# muhtas3.net
KiCad netlist of a schematic drawn in Altium Designer
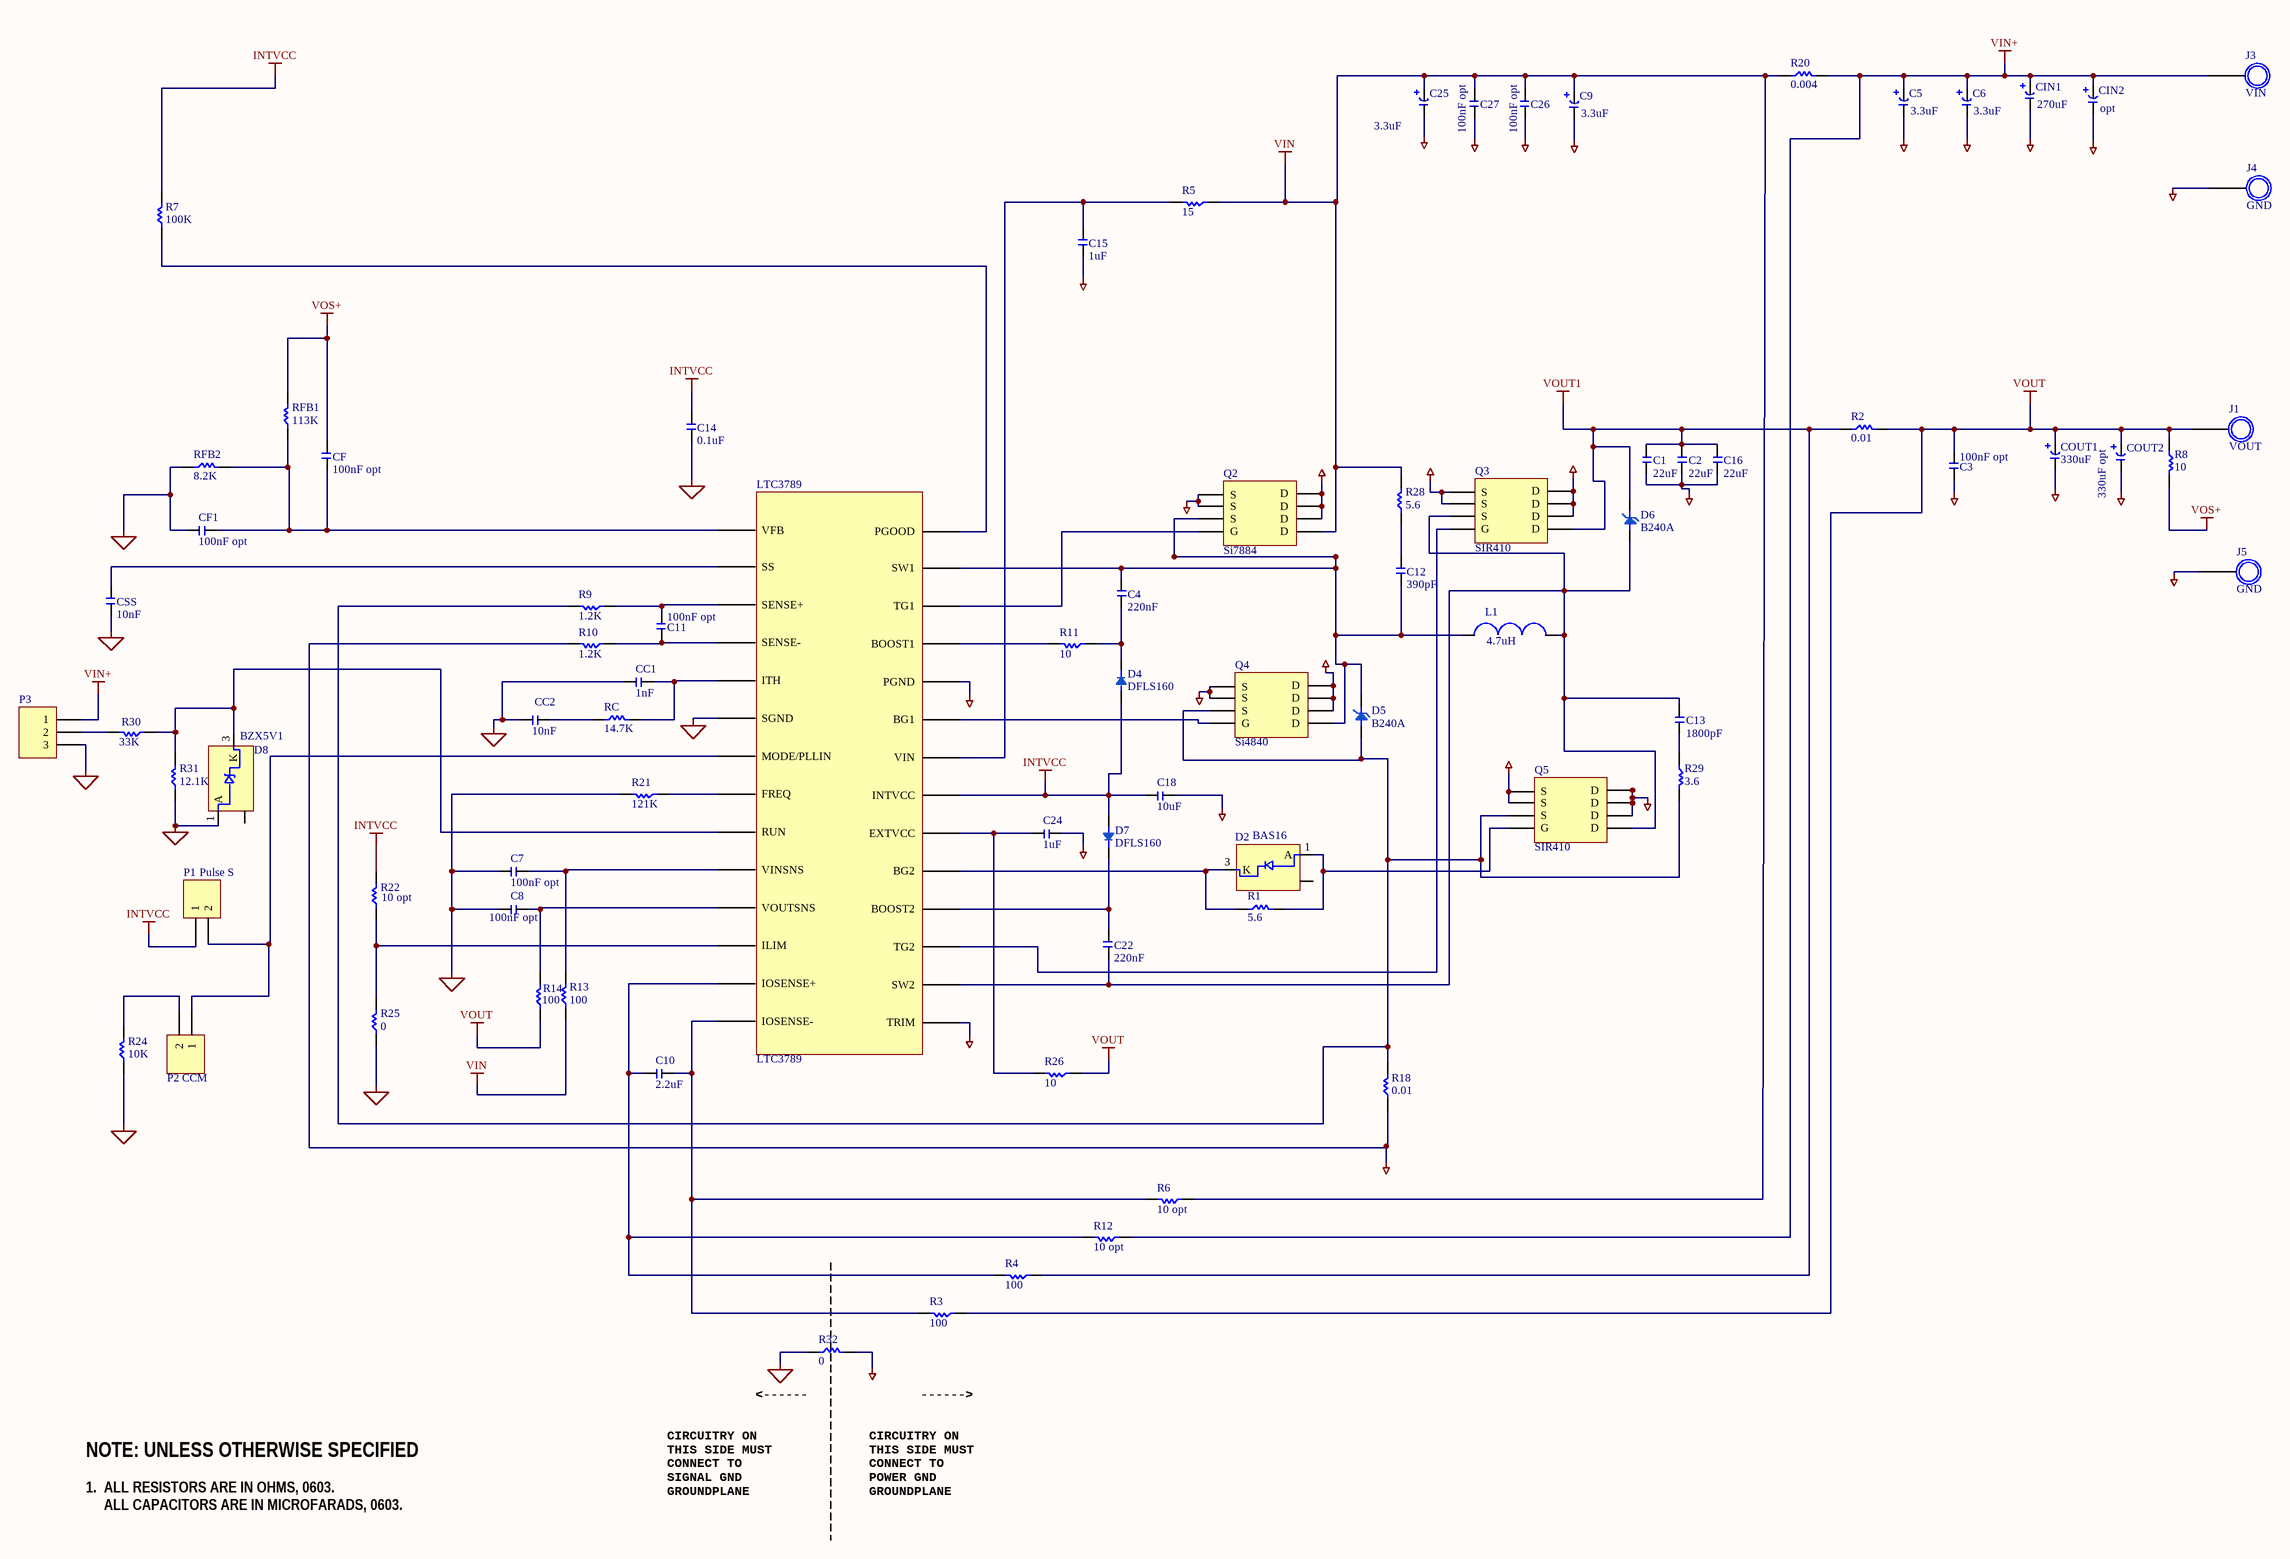
[diagram p0: muhtas3.SchDoc]

(export (version "E")
  (design (tool "Eeschema 10.0.6"))
  (components
    (comp (ref "C1")
      (value "22uF")
      (footprint "CAPC3216X190N(1206)")
      (fields
        (field (name "MANUFACTURER PART NUMBER") "VJ1206G475KXQTW1BC")
        (field (name "MANUFACTURER") "Vishay Vitramon")
        (field (name "TOLERANCE") "10%")
      )
      (libsource (lib "Database_Libs1") (part "Capacitor-non polarized"))
    )
    (comp (ref "C2")
      (value "22uF")
      (footprint "CAPC3216X190N(1206)")
      (fields
        (field (name "MANUFACTURER PART NUMBER") "VJ1206G475KXQTW1BC")
        (field (name "MANUFACTURER") "Vishay Vitramon")
        (field (name "TOLERANCE") "10%")
      )
      (libsource (lib "Database_Libs1") (part "Capacitor-non polarized"))
    )
    (comp (ref "C3")
      (value "100nF opt")
      (footprint "CAPC3216X190N(1206)")
      (fields
        (field (name "MANUFACTURER PART NUMBER") "VJ1206G475KXQTW1BC")
        (field (name "MANUFACTURER") "Vishay Vitramon")
        (field (name "TOLERANCE") "10%")
      )
      (libsource (lib "Database_Libs1") (part "Capacitor-non polarized"))
    )
    (comp (ref "C4")
      (value "220nF")
      (footprint "CAPC2012X14N(0805)")
      (description "TDK - CGA3E2X7R1H104K080AA. - CERAMIC CAPACITOR, 0.1UF, 50V, X7R, 0603, FULL REEL")
      (fields (field (name "MANUFACTURER PART NUMBER") "CAP CER 100NF") (field (name "MANUFACTURER") "TDK"))
      (libsource (lib "Database_Libs1") (part "Capacitor-non polarized"))
    )
    (comp (ref "C5")
      (value "3.3uF")
      (footprint "RAD5X10X16")
      (fields
        (field (name "MANUFACTURER PART NUMBER") "CAP EL 470UF")
        (field (name "MANUFACTURER") "Nichicon")
        (field (name "TOLERANCE") "20%")
      )
      (libsource (lib "Database_Libs1") (part "Capacitor-polarized"))
    )
    (comp (ref "C6")
      (value "3.3uF")
      (footprint "RAD5X10X16")
      (fields
        (field (name "MANUFACTURER PART NUMBER") "CAP EL 470UF")
        (field (name "MANUFACTURER") "Nichicon")
        (field (name "TOLERANCE") "20%")
      )
      (libsource (lib "Database_Libs1") (part "Capacitor-polarized"))
    )
    (comp (ref "C7")
      (value "100nF opt")
      (footprint "CAPC3216X190N(1206)")
      (fields
        (field (name "MANUFACTURER PART NUMBER") "VJ1206G475KXQTW1BC")
        (field (name "MANUFACTURER") "Vishay Vitramon")
        (field (name "TOLERANCE") "10%")
      )
      (libsource (lib "Database_Libs1") (part "Capacitor-non polarized"))
    )
    (comp (ref "C8")
      (value "100nF opt")
      (footprint "CAPC3216X190N(1206)")
      (fields
        (field (name "MANUFACTURER PART NUMBER") "VJ1206G475KXQTW1BC")
        (field (name "MANUFACTURER") "Vishay Vitramon")
        (field (name "TOLERANCE") "10%")
      )
      (libsource (lib "Database_Libs1") (part "Capacitor-non polarized"))
    )
    (comp (ref "C9")
      (value "3.3uF")
      (footprint "RAD5X10X16")
      (fields
        (field (name "MANUFACTURER PART NUMBER") "CAP EL 470UF")
        (field (name "MANUFACTURER") "Nichicon")
        (field (name "TOLERANCE") "20%")
      )
      (libsource (lib "Database_Libs1") (part "Capacitor-polarized"))
    )
    (comp (ref "C10")
      (value "2.2uF")
      (footprint "CAPC3216X190N(1206)")
      (fields
        (field (name "MANUFACTURER PART NUMBER") "VJ1206G475KXQTW1BC")
        (field (name "MANUFACTURER") "Vishay Vitramon")
        (field (name "TOLERANCE") "10%")
      )
      (libsource (lib "Database_Libs1") (part "Capacitor-non polarized"))
    )
    (comp (ref "C11")
      (value "100nF opt")
      (footprint "CAPC3216X190N(1206)")
      (fields
        (field (name "MANUFACTURER PART NUMBER") "VJ1206G475KXQTW1BC")
        (field (name "MANUFACTURER") "Vishay Vitramon")
        (field (name "TOLERANCE") "10%")
      )
      (libsource (lib "Database_Libs1") (part "Capacitor-non polarized"))
    )
    (comp (ref "C12")
      (value "390pF")
      (footprint "2.54X5.5MM")
      (fields
        (field (name "MANUFACTURER PART NUMBER") "CAP CER DISC 220PF")
        (field (name "MANUFACTURER") "KEMET")
        (field (name "TOLERANCE") "10%")
      )
      (libsource (lib "Database_Libs1") (part "Capacitor-non polarized"))
    )
    (comp (ref "C13")
      (value "1800pF")
      (footprint "CAPC3216X190N(1206)")
      (fields
        (field (name "MANUFACTURER PART NUMBER") "VJ1206G475KXQTW1BC")
        (field (name "MANUFACTURER") "Vishay Vitramon")
        (field (name "TOLERANCE") "10%")
      )
      (libsource (lib "Database_Libs1") (part "Capacitor-non polarized"))
    )
    (comp (ref "C14")
      (value "0.1uF")
      (footprint "CAPC3216X190N(1206)")
      (fields
        (field (name "MANUFACTURER PART NUMBER") "VJ1206G475KXQTW1BC")
        (field (name "MANUFACTURER") "Vishay Vitramon")
        (field (name "TOLERANCE") "10%")
      )
      (libsource (lib "Database_Libs1") (part "Capacitor-non polarized"))
    )
    (comp (ref "C15")
      (value "1uF")
      (footprint "CAPC3216X190N(1206)")
      (fields
        (field (name "MANUFACTURER PART NUMBER") "VJ1206G475KXQTW1BC")
        (field (name "MANUFACTURER") "Vishay Vitramon")
        (field (name "TOLERANCE") "10%")
      )
      (libsource (lib "Database_Libs1") (part "Capacitor-non polarized"))
    )
    (comp (ref "C16")
      (value "22uF")
      (footprint "CAPC3216X190N(1206)")
      (fields
        (field (name "MANUFACTURER PART NUMBER") "VJ1206G475KXQTW1BC")
        (field (name "MANUFACTURER") "Vishay Vitramon")
        (field (name "TOLERANCE") "10%")
      )
      (libsource (lib "Database_Libs1") (part "Capacitor-non polarized"))
    )
    (comp (ref "C18")
      (value "10uF")
      (footprint "CAPC2012X14N(0805)")
      (description "TDK - CGA3E2X7R1H104K080AA. - CERAMIC CAPACITOR, 0.1UF, 50V, X7R, 0603, FULL REEL")
      (fields (field (name "MANUFACTURER PART NUMBER") "CAP CER 100NF") (field (name "MANUFACTURER") "TDK"))
      (libsource (lib "Database_Libs1") (part "Capacitor-non polarized"))
    )
    (comp (ref "C22")
      (value "220nF")
      (footprint "CAPC2012X14N(0805)")
      (description "TDK - CGA3E2X7R1H104K080AA. - CERAMIC CAPACITOR, 0.1UF, 50V, X7R, 0603, FULL REEL")
      (fields (field (name "MANUFACTURER PART NUMBER") "CAP CER 100NF") (field (name "MANUFACTURER") "TDK"))
      (libsource (lib "Database_Libs1") (part "Capacitor-non polarized"))
    )
    (comp (ref "C24")
      (value "1uF")
      (footprint "CAPC2012X14N(0805)")
      (description "TDK - CGA3E2X7R1H104K080AA. - CERAMIC CAPACITOR, 0.1UF, 50V, X7R, 0603, FULL REEL")
      (fields (field (name "MANUFACTURER PART NUMBER") "CAP CER 100NF") (field (name "MANUFACTURER") "TDK"))
      (libsource (lib "Database_Libs1") (part "Capacitor-non polarized"))
    )
    (comp (ref "C25")
      (value "3.3uF")
      (footprint "RAD5X10X16")
      (fields
        (field (name "MANUFACTURER PART NUMBER") "CAP EL 470UF")
        (field (name "MANUFACTURER") "Nichicon")
        (field (name "TOLERANCE") "20%")
      )
      (libsource (lib "Database_Libs1") (part "Capacitor-polarized"))
    )
    (comp (ref "C26")
      (value "100nF opt")
      (footprint "CAPC3216X190N(1206)")
      (fields
        (field (name "MANUFACTURER PART NUMBER") "VJ1206G475KXQTW1BC")
        (field (name "MANUFACTURER") "Vishay Vitramon")
        (field (name "TOLERANCE") "10%")
      )
      (libsource (lib "Database_Libs1") (part "Capacitor-non polarized"))
    )
    (comp (ref "C27")
      (value "100nF opt")
      (footprint "CAPC3216X190N(1206)")
      (fields
        (field (name "MANUFACTURER PART NUMBER") "VJ1206G475KXQTW1BC")
        (field (name "MANUFACTURER") "Vishay Vitramon")
        (field (name "TOLERANCE") "10%")
      )
      (libsource (lib "Database_Libs1") (part "Capacitor-non polarized"))
    )
    (comp (ref "CC1")
      (value "1nF")
      (footprint "CAPC3216X190N(1206)")
      (fields
        (field (name "MANUFACTURER PART NUMBER") "VJ1206G475KXQTW1BC")
        (field (name "MANUFACTURER") "Vishay Vitramon")
        (field (name "TOLERANCE") "10%")
      )
      (libsource (lib "Database_Libs1") (part "Capacitor-non polarized"))
    )
    (comp (ref "CC2")
      (value "10nF")
      (footprint "CAPC3216X190N(1206)")
      (fields
        (field (name "MANUFACTURER PART NUMBER") "VJ1206G475KXQTW1BC")
        (field (name "MANUFACTURER") "Vishay Vitramon")
        (field (name "TOLERANCE") "10%")
      )
      (libsource (lib "Database_Libs1") (part "Capacitor-non polarized"))
    )
    (comp (ref "CF")
      (value "100nF opt")
      (footprint "CAPC3216X190N(1206)")
      (fields
        (field (name "MANUFACTURER PART NUMBER") "VJ1206G475KXQTW1BC")
        (field (name "MANUFACTURER") "Vishay Vitramon")
        (field (name "TOLERANCE") "10%")
      )
      (libsource (lib "Database_Libs1") (part "Capacitor-non polarized"))
    )
    (comp (ref "CF1")
      (value "100nF opt")
      (footprint "CAPC3216X190N(1206)")
      (fields
        (field (name "MANUFACTURER PART NUMBER") "VJ1206G475KXQTW1BC")
        (field (name "MANUFACTURER") "Vishay Vitramon")
        (field (name "TOLERANCE") "10%")
      )
      (libsource (lib "Database_Libs1") (part "Capacitor-non polarized"))
    )
    (comp (ref "CIN1")
      (value "270uF")
      (footprint "RAD5X10X16")
      (fields
        (field (name "MANUFACTURER PART NUMBER") "CAP EL 470UF")
        (field (name "MANUFACTURER") "Nichicon")
        (field (name "TOLERANCE") "20%")
      )
      (libsource (lib "Database_Libs1") (part "Capacitor-polarized"))
    )
    (comp (ref "CIN2")
      (value "opt")
      (footprint "RAD5X10X16")
      (fields
        (field (name "MANUFACTURER PART NUMBER") "CAP EL 470UF")
        (field (name "MANUFACTURER") "Nichicon")
        (field (name "TOLERANCE") "20%")
      )
      (libsource (lib "Database_Libs1") (part "Capacitor-polarized"))
    )
    (comp (ref "COUT1")
      (value "330uF")
      (footprint "OSCON")
      (description "CAP ALUM POLY 180UF 20% 16V T/H")
      (fields
        (field (name "MANUFACTURER PART NUMBER") "16SEPC180MX")
        (field (name "MANUFACTURER") "Panasonic")
      )
      (libsource (lib "Database_Libs1") (part "Capacitor-polarized"))
    )
    (comp (ref "COUT2")
      (value "330uF opt")
      (footprint "OSCON")
      (description "CAP ALUM POLY 180UF 20% 16V T/H")
      (fields
        (field (name "MANUFACTURER PART NUMBER") "16SEPC180MX")
        (field (name "MANUFACTURER") "Panasonic")
      )
      (libsource (lib "Database_Libs1") (part "Capacitor-polarized"))
    )
    (comp (ref "CSS")
      (value "10nF")
      (footprint "CAPC3216X190N(1206)")
      (fields
        (field (name "MANUFACTURER PART NUMBER") "VJ1206G475KXQTW1BC")
        (field (name "MANUFACTURER") "Vishay Vitramon")
        (field (name "TOLERANCE") "10%")
      )
      (libsource (lib "Database_Libs1") (part "Capacitor-non polarized"))
    )
    (comp (ref "D2")
      (value "BAS16")
      (footprint "BZX5V1/SOT23")
      (description "MOSFET 20V 35A 36W")
      (fields
        (field (name "MANUFACTURER PART NUMBER") "SIR410DP-T1-GE3")
        (field (name "MANUFACTURER") "Vishay Siliconix")
      )
      (libsource (lib "Database_Libs1") (part "BAS16"))
    )
    (comp (ref "D4")
      (value "DFLS160")
      (footprint "DFLS160")
      (description "DIODE SCHOTTKY 60V 1A POWERDI123")
      (fields (field (name "MANUFACTURER PART NUMBER") "DFLS160Q-7") (field (name "MANUFACTURER") "Diodes"))
      (libsource (lib "Database_Libs1") (part "Diode"))
    )
    (comp (ref "D5")
      (value "B240A")
      (footprint "B240A")
      (description "DIODES INC. - B240-13-F - Schottky Rectifier, 40 V, 2 A, Single, DO-214AA (SMB), 2 Pins, 500 mV")
      (fields (field (name "MANUFACTURER PART NUMBER") "B240-13-F") (field (name "MANUFACTURER") "Diodes"))
      (libsource (lib "Database_Libs1") (part "Diode-zener"))
    )
    (comp (ref "D6")
      (value "B240A")
      (footprint "B240A")
      (description "DIODES INC. - B240-13-F - Schottky Rectifier, 40 V, 2 A, Single, DO-214AA (SMB), 2 Pins, 500 mV")
      (fields (field (name "MANUFACTURER PART NUMBER") "B240-13-F") (field (name "MANUFACTURER") "Diodes"))
      (libsource (lib "Database_Libs1") (part "Diode-zener"))
    )
    (comp (ref "D7")
      (value "DFLS160")
      (footprint "DFLS160")
      (description "DIODE SCHOTTKY 60V 1A POWERDI123")
      (fields (field (name "MANUFACTURER PART NUMBER") "DFLS160Q-7") (field (name "MANUFACTURER") "Diodes"))
      (libsource (lib "Database_Libs1") (part "Diode"))
    )
    (comp (ref "D8")
      (value "BZX5V1")
      (footprint "BZX5V1/SOT23")
      (description "Diode Zener Single 5.1V 2% 300mW 3-Pin SOT-23 T/R")
      (fields
        (field (name "MANUFACTURER PART NUMBER") "BZX84B5V1LT1G")
        (field (name "MANUFACTURER") "ON Semiconductor")
      )
      (libsource (lib "Database_Libs1") (part "BZX5V1"))
    )
    (comp (ref "J1")
      (value "VOUT")
      (footprint "I/O")
      (description "SWITCH SLIDE DIP SPST 150MA 30V")
      (fields (field (name "MANUFACTURER PART NUMBER") "78B03ST") (field (name "MANUFACTURER") "Grayhill"))
      (libsource (lib "Database_Libs1") (part "I/O"))
    )
    (comp (ref "J3")
      (value "VIN")
      (footprint "I/O")
      (description "SWITCH SLIDE DIP SPST 150MA 30V")
      (fields (field (name "MANUFACTURER PART NUMBER") "78B03ST") (field (name "MANUFACTURER") "Grayhill"))
      (libsource (lib "Database_Libs1") (part "I/O"))
    )
    (comp (ref "J4")
      (value "GND")
      (footprint "I/O")
      (description "SWITCH SLIDE DIP SPST 150MA 30V")
      (fields (field (name "MANUFACTURER PART NUMBER") "78B03ST") (field (name "MANUFACTURER") "Grayhill"))
      (libsource (lib "Database_Libs1") (part "I/O"))
    )
    (comp (ref "J5")
      (value "GND")
      (footprint "I/O")
      (description "SWITCH SLIDE DIP SPST 150MA 30V")
      (fields (field (name "MANUFACTURER PART NUMBER") "78B03ST") (field (name "MANUFACTURER") "Grayhill"))
      (libsource (lib "Database_Libs1") (part "I/O"))
    )
    (comp (ref "L1")
      (value "4.7uH")
      (footprint "4.7UH")
      (description "Inductor Power Shielded Wirewound 4.7uH 20% 100KHz 5.5A 40mOhm DCR 2525 T/R")
      (fields
        (field (name "MANUFACTURER PART NUMBER") "IHLP2525CZER4R7M01")
        (field (name "MANUFACTURER") "Vishay Dale")
      )
      (libsource (lib "Database_Libs1") (part "Bobin"))
    )
    (comp (ref "LTC3789")
      (value "LTC3789")
      (footprint "LTC3789")
      (description "DC DC Cntrlr Dual-OUT Synchronous Boost/Buck Controller 4V to 38V Input Automotive 28-Pin SSOP N")
      (fields
        (field (name "MANUFACTURER PART NUMBER") "LTC3789EGN#PBF")
        (field (name "MANUFACTURER") "Analog Devices / Linear Technology")
      )
      (libsource (lib "Database_Libs1") (part "LTC3789"))
    )
    (comp (ref "P1")
      (value "Header 2")
      (footprint "HDR1X2")
      (description "Header, 2-Pin")
      (fields (field (name "PUBLISHER") "Altium Limited"))
      (libsource (lib "Miscellaneous Connectors") (part "Header 2"))
    )
    (comp (ref "P2")
      (value "Header 2")
      (footprint "HDR1X2")
      (description "Header, 2-Pin")
      (fields (field (name "PUBLISHER") "Altium Limited"))
      (libsource (lib "") (part "Header 2_1"))
    )
    (comp (ref "P3")
      (value "Header 3")
      (footprint "HDR1X3")
      (description "Header, 3-Pin")
      (fields (field (name "PUBLISHER") "Altium Limited"))
      (libsource (lib "Miscellaneous Connectors") (part "Header 3"))
    )
    (comp (ref "Q2")
      (value "Si7884")
      (footprint "MOSFET")
      (description "MOSFET 20V 35A 36W")
      (fields
        (field (name "MANUFACTURER PART NUMBER") "SIR410DP-T1-GE3")
        (field (name "MANUFACTURER") "Vishay Siliconix")
      )
      (libsource (lib "Database_Libs1") (part "8-Mosfet"))
    )
    (comp (ref "Q3")
      (value "SIR410")
      (footprint "MOSFET")
      (description "MOSFET 20V 35A 36W")
      (fields
        (field (name "MANUFACTURER PART NUMBER") "SIR410DP-T1-GE3")
        (field (name "MANUFACTURER") "Vishay Siliconix")
      )
      (libsource (lib "Database_Libs1") (part "8-Mosfet"))
    )
    (comp (ref "Q4")
      (value "Si4840")
      (footprint "SOIC-8-SI4840")
      (description "MOSFET N-CH 40V 10A 8-SOIC")
      (fields
        (field (name "MANUFACTURER PART NUMBER") "SI4840DY-T1-E3")
        (field (name "MANUFACTURER") "Vishay Siliconix")
      )
      (libsource (lib "Database_Libs1") (part "8-Mosfet"))
    )
    (comp (ref "Q5")
      (value "SIR410")
      (footprint "MOSFET")
      (description "MOSFET 20V 35A 36W")
      (fields
        (field (name "MANUFACTURER PART NUMBER") "SIR410DP-T1-GE3")
        (field (name "MANUFACTURER") "Vishay Siliconix")
      )
      (libsource (lib "Database_Libs1") (part "8-Mosfet"))
    )
    (comp (ref "R1")
      (value "5.6")
      (footprint "RESC2013X70N(0805)")
      (description "Res Thick Film 0805 47K Ohm 5% 1/8W ±100ppm/°C Molded SMD T/R")
      (fields
        (field (name "MANUFACTURER PART NUMBER") "RC2012J473AS")
        (field (name "MANUFACTURER") "Samsung")
      )
      (libsource (lib "Database_Libs1") (part "Resistor"))
    )
    (comp (ref "R2")
      (value "0.01")
      (footprint "SUSUMU")
      (fields
        (field (name "MANUFACTURER PART NUMBER") "RL1220S-R50-F")
        (field (name "MANUFACTURER") "Susumu")
        (field (name "TOLERANCE") "1%")
      )
      (libsource (lib "Database_Libs1") (part "Resistor"))
    )
    (comp (ref "R3")
      (value "100")
      (footprint "RESC3216X84N(1206)")
      (description "Resistor,Metal Glaze,56KOhms,200WV,5+/-% Tol,-200,200ppm-TC,1206-Case ;RoHS Compliant: Yes")
      (fields
        (field (name "MANUFACTURER PART NUMBER") "RES  56K 1/4W")
        (field (name "MANUFACTURER") "Vishay Dale")
      )
      (libsource (lib "Database_Libs1") (part "Resistor"))
    )
    (comp (ref "R4")
      (value "100")
      (footprint "RESC3216X84N(1206)")
      (description "Resistor,Metal Glaze,56KOhms,200WV,5+/-% Tol,-200,200ppm-TC,1206-Case ;RoHS Compliant: Yes")
      (fields
        (field (name "MANUFACTURER PART NUMBER") "RES  56K 1/4W")
        (field (name "MANUFACTURER") "Vishay Dale")
      )
      (libsource (lib "Database_Libs1") (part "Resistor"))
    )
    (comp (ref "R5")
      (value "15")
      (footprint "RESC3216X84N(1206)")
      (description "Resistor,Metal Glaze,56KOhms,200WV,5+/-% Tol,-200,200ppm-TC,1206-Case ;RoHS Compliant: Yes")
      (fields
        (field (name "MANUFACTURER PART NUMBER") "RES  56K 1/4W")
        (field (name "MANUFACTURER") "Vishay Dale")
      )
      (libsource (lib "Database_Libs1") (part "Resistor"))
    )
    (comp (ref "R6")
      (value "10 opt")
      (footprint "RESC3216X84N(1206)")
      (description "Resistor,Metal Glaze,56KOhms,200WV,5+/-% Tol,-200,200ppm-TC,1206-Case ;RoHS Compliant: Yes")
      (fields
        (field (name "MANUFACTURER PART NUMBER") "RES  56K 1/4W")
        (field (name "MANUFACTURER") "Vishay Dale")
      )
      (libsource (lib "Database_Libs1") (part "Resistor"))
    )
    (comp (ref "R7")
      (value "100K")
      (footprint "RESC3216X84N(1206)")
      (description "Resistor,Metal Glaze,56KOhms,200WV,5+/-% Tol,-200,200ppm-TC,1206-Case ;RoHS Compliant: Yes")
      (fields
        (field (name "MANUFACTURER PART NUMBER") "RES  56K 1/4W")
        (field (name "MANUFACTURER") "Vishay Dale")
      )
      (libsource (lib "Database_Libs1") (part "Resistor"))
    )
    (comp (ref "R8")
      (value "10")
      (footprint "RESC3216X84N(1206)")
      (description "Resistor,Metal Glaze,56KOhms,200WV,5+/-% Tol,-200,200ppm-TC,1206-Case ;RoHS Compliant: Yes")
      (fields
        (field (name "MANUFACTURER PART NUMBER") "RES  56K 1/4W")
        (field (name "MANUFACTURER") "Vishay Dale")
      )
      (libsource (lib "Database_Libs1") (part "Resistor"))
    )
    (comp (ref "R9")
      (value "1.2K")
      (footprint "AXIAL0.4")
      (description "Resistor; Thick Film; 270 Ohms; 0.125 W; 1%; SMT; 0805; TCR 37 ppm/DegC; Tape and Reel")
      (fields
        (field (name "MANUFACTURER PART NUMBER") "CRCW0805270RFKEA")
        (field (name "MANUFACTURER") "Vishay")
      )
      (libsource (lib "Database_Libs1") (part "Resistor"))
    )
    (comp (ref "R10")
      (value "1.2K")
      (footprint "AXIAL0.4")
      (description "Resistor; Thick Film; 270 Ohms; 0.125 W; 1%; SMT; 0805; TCR 37 ppm/DegC; Tape and Reel")
      (fields
        (field (name "MANUFACTURER PART NUMBER") "CRCW0805270RFKEA")
        (field (name "MANUFACTURER") "Vishay")
      )
      (libsource (lib "Database_Libs1") (part "Resistor"))
    )
    (comp (ref "R11")
      (value "10")
      (footprint "RESC3216X84N(1206)")
      (description "Resistor,Metal Glaze,56KOhms,200WV,5+/-% Tol,-200,200ppm-TC,1206-Case ;RoHS Compliant: Yes")
      (fields
        (field (name "MANUFACTURER PART NUMBER") "RES  56K 1/4W")
        (field (name "MANUFACTURER") "Vishay Dale")
      )
      (libsource (lib "Database_Libs1") (part "Resistor"))
    )
    (comp (ref "R12")
      (value "10 opt")
      (footprint "RESC3216X84N(1206)")
      (description "Resistor,Metal Glaze,56KOhms,200WV,5+/-% Tol,-200,200ppm-TC,1206-Case ;RoHS Compliant: Yes")
      (fields
        (field (name "MANUFACTURER PART NUMBER") "RES  56K 1/4W")
        (field (name "MANUFACTURER") "Vishay Dale")
      )
      (libsource (lib "Database_Libs1") (part "Resistor"))
    )
    (comp (ref "R13")
      (value "100")
      (footprint "RESC3216X84N(1206)")
      (description "Resistor,Metal Glaze,56KOhms,200WV,5+/-% Tol,-200,200ppm-TC,1206-Case ;RoHS Compliant: Yes")
      (fields
        (field (name "MANUFACTURER PART NUMBER") "RES  56K 1/4W")
        (field (name "MANUFACTURER") "Vishay Dale")
      )
      (libsource (lib "Database_Libs1") (part "Resistor"))
    )
    (comp (ref "R14")
      (value "100")
      (footprint "RESC3216X84N(1206)")
      (description "Resistor,Metal Glaze,56KOhms,200WV,5+/-% Tol,-200,200ppm-TC,1206-Case ;RoHS Compliant: Yes")
      (fields
        (field (name "MANUFACTURER PART NUMBER") "RES  56K 1/4W")
        (field (name "MANUFACTURER") "Vishay Dale")
      )
      (libsource (lib "Database_Libs1") (part "Resistor"))
    )
    (comp (ref "R18")
      (value "0.01")
      (footprint "SUSUMU")
      (fields
        (field (name "MANUFACTURER PART NUMBER") "RL1220S-R50-F")
        (field (name "MANUFACTURER") "Susumu")
        (field (name "TOLERANCE") "1%")
      )
      (libsource (lib "Database_Libs1") (part "Resistor"))
    )
    (comp (ref "R20")
      (value "0.004")
      (footprint "SUSUMU")
      (fields
        (field (name "MANUFACTURER PART NUMBER") "RL1220S-R50-F")
        (field (name "MANUFACTURER") "Susumu")
        (field (name "TOLERANCE") "1%")
      )
      (libsource (lib "Database_Libs1") (part "Resistor"))
    )
    (comp (ref "R21")
      (value "121K")
      (footprint "AXIAL0.4")
      (description "Resistor; Thick Film; 270 Ohms; 0.125 W; 1%; SMT; 0805; TCR 37 ppm/DegC; Tape and Reel")
      (fields
        (field (name "MANUFACTURER PART NUMBER") "CRCW0805270RFKEA")
        (field (name "MANUFACTURER") "Vishay")
      )
      (libsource (lib "Database_Libs1") (part "Resistor"))
    )
    (comp (ref "R22")
      (value "10 opt")
      (footprint "RESC3216X84N(1206)")
      (description "Resistor,Metal Glaze,56KOhms,200WV,5+/-% Tol,-200,200ppm-TC,1206-Case ;RoHS Compliant: Yes")
      (fields
        (field (name "MANUFACTURER PART NUMBER") "RES  56K 1/4W")
        (field (name "MANUFACTURER") "Vishay Dale")
      )
      (libsource (lib "Database_Libs1") (part "Resistor"))
    )
    (comp (ref "R24")
      (value "10K")
      (footprint "RESC3216X84N(1206)")
      (description "Resistor,Metal Glaze,56KOhms,200WV,5+/-% Tol,-200,200ppm-TC,1206-Case ;RoHS Compliant: Yes")
      (fields
        (field (name "MANUFACTURER PART NUMBER") "RES  56K 1/4W")
        (field (name "MANUFACTURER") "Vishay Dale")
      )
      (libsource (lib "Database_Libs1") (part "Resistor"))
    )
    (comp (ref "R25")
      (value "0")
      (footprint "RESC2013X70N(0805)")
      (description "Res Thick Film 0805 47K Ohm 5% 1/8W ±100ppm/°C Molded SMD T/R")
      (fields
        (field (name "MANUFACTURER PART NUMBER") "RC2012J473AS")
        (field (name "MANUFACTURER") "Samsung")
      )
      (libsource (lib "Database_Libs1") (part "Resistor"))
    )
    (comp (ref "R26")
      (value "10")
      (footprint "RESC3216X84N(1206)")
      (description "Resistor,Metal Glaze,56KOhms,200WV,5+/-% Tol,-200,200ppm-TC,1206-Case ;RoHS Compliant: Yes")
      (fields
        (field (name "MANUFACTURER PART NUMBER") "RES  56K 1/4W")
        (field (name "MANUFACTURER") "Vishay Dale")
      )
      (libsource (lib "Database_Libs1") (part "Resistor"))
    )
    (comp (ref "R28")
      (value "5.6")
      (footprint "RESC2013X70N(0805)")
      (description "Res Thick Film 0805 47K Ohm 5% 1/8W ±100ppm/°C Molded SMD T/R")
      (fields
        (field (name "MANUFACTURER PART NUMBER") "RC2012J473AS")
        (field (name "MANUFACTURER") "Samsung")
      )
      (libsource (lib "Database_Libs1") (part "Resistor"))
    )
    (comp (ref "R29")
      (value "3.6")
      (footprint "RESC3216X84N(1206)")
      (description "Resistor,Metal Glaze,56KOhms,200WV,5+/-% Tol,-200,200ppm-TC,1206-Case ;RoHS Compliant: Yes")
      (fields
        (field (name "MANUFACTURER PART NUMBER") "RES  56K 1/4W")
        (field (name "MANUFACTURER") "Vishay Dale")
      )
      (libsource (lib "Database_Libs1") (part "Resistor"))
    )
    (comp (ref "R30")
      (value "33K")
      (footprint "RESC3216X84N(1206)")
      (description "Resistor,Metal Glaze,56KOhms,200WV,5+/-% Tol,-200,200ppm-TC,1206-Case ;RoHS Compliant: Yes")
      (fields
        (field (name "MANUFACTURER PART NUMBER") "RES  56K 1/4W")
        (field (name "MANUFACTURER") "Vishay Dale")
      )
      (libsource (lib "Database_Libs1") (part "Resistor"))
    )
    (comp (ref "R31")
      (value "12.1K")
      (footprint "RESC2013X70N(0805)")
      (description "Res Thick Film 0805 47K Ohm 5% 1/8W ±100ppm/°C Molded SMD T/R")
      (fields
        (field (name "MANUFACTURER PART NUMBER") "RC2012J473AS")
        (field (name "MANUFACTURER") "Samsung")
      )
      (libsource (lib "Database_Libs1") (part "Resistor"))
    )
    (comp (ref "R32")
      (value "0")
      (footprint "RESC2013X70N(0805)")
      (description "Res Thick Film 0805 47K Ohm 5% 1/8W ±100ppm/°C Molded SMD T/R")
      (fields
        (field (name "MANUFACTURER PART NUMBER") "RC2012J473AS")
        (field (name "MANUFACTURER") "Samsung")
      )
      (libsource (lib "Database_Libs1") (part "Resistor"))
    )
    (comp (ref "RC")
      (value "14.7K")
      (footprint "RESC2013X70N(0805)")
      (description "Res Thick Film 0805 25.5 Ohm 1% 1/4W 300ppm/C Molded SMD Punched Carrier T/R")
      (fields
        (field (name "MANUFACTURER PART NUMBER") "ERJ-P06F25R5V")
        (field (name "MANUFACTURER") "Panasonic")
      )
      (libsource (lib "Database_Libs1") (part "Resistor"))
    )
    (comp (ref "RFB1")
      (value "113K")
      (footprint "AXIAL0.4")
      (description "Resistor; Thick Film; 270 Ohms; 0.125 W; 1%; SMT; 0805; TCR 37 ppm/DegC; Tape and Reel")
      (fields
        (field (name "MANUFACTURER PART NUMBER") "CRCW0805270RFKEA")
        (field (name "MANUFACTURER") "Vishay")
      )
      (libsource (lib "Database_Libs1") (part "Resistor"))
    )
    (comp (ref "RFB2")
      (value "8.2K")
      (footprint "RESC2013X70N(0805)")
      (description "Res Thick Film 0805 25.5 Ohm 1% 1/4W 300ppm/C Molded SMD Punched Carrier T/R")
      (fields
        (field (name "MANUFACTURER PART NUMBER") "ERJ-P06F25R5V")
        (field (name "MANUFACTURER") "Panasonic")
      )
      (libsource (lib "Database_Libs1") (part "Resistor"))
    )
  )
  (nets
    (net (code "1") (name "GND") (class "Default")
      (node (ref "C1") (pin "1") (pinfunction "1_1") (pintype "passive"))
      (node (ref "C15") (pin "2") (pinfunction "2_2") (pintype "passive"))
      (node (ref "C16") (pin "1") (pinfunction "1_1") (pintype "passive"))
      (node (ref "C18") (pin "2") (pinfunction "2_2") (pintype "passive"))
      (node (ref "C2") (pin "1") (pinfunction "1_1") (pintype "passive"))
      (node (ref "C24") (pin "2") (pinfunction "2_2") (pintype "passive"))
      (node (ref "C25") (pin "2") (pinfunction "K_2") (pintype "passive"))
      (node (ref "C26") (pin "2") (pinfunction "2_2") (pintype "passive"))
      (node (ref "C27") (pin "2") (pinfunction "2_2") (pintype "passive"))
      (node (ref "C3") (pin "2") (pinfunction "2_2") (pintype "passive"))
      (node (ref "C5") (pin "2") (pinfunction "K_2") (pintype "passive"))
      (node (ref "C6") (pin "2") (pinfunction "K_2") (pintype "passive"))
      (node (ref "C9") (pin "2") (pinfunction "K_2") (pintype "passive"))
      (node (ref "CIN1") (pin "2") (pinfunction "K_2") (pintype "passive"))
      (node (ref "CIN2") (pin "2") (pinfunction "K_2") (pintype "passive"))
      (node (ref "COUT1") (pin "2") (pinfunction "K_2") (pintype "passive"))
      (node (ref "COUT2") (pin "2") (pinfunction "K_2") (pintype "passive"))
      (node (ref "J4") (pin "1") (pinfunction "1_1") (pintype "passive"))
      (node (ref "J5") (pin "1") (pinfunction "1_1") (pintype "passive"))
      (node (ref "LTC3789") (pin "15") (pinfunction "TRIM_15") (pintype "passive"))
      (node (ref "LTC3789") (pin "24") (pinfunction "PGND_24") (pintype "passive"))
      (node (ref "Q2") (pin "1") (pinfunction "S_1") (pintype "passive"))
      (node (ref "Q2") (pin "2") (pinfunction "S_2") (pintype "passive"))
      (node (ref "Q2") (pin "6") (pinfunction "D_6") (pintype "passive"))
      (node (ref "Q2") (pin "7") (pinfunction "D_7") (pintype "passive"))
      (node (ref "Q2") (pin "8") (pinfunction "D_8") (pintype "passive"))
      (node (ref "Q3") (pin "1") (pinfunction "S_1") (pintype "passive"))
      (node (ref "Q3") (pin "2") (pinfunction "S_2") (pintype "passive"))
      (node (ref "Q3") (pin "6") (pinfunction "D_6") (pintype "passive"))
      (node (ref "Q3") (pin "7") (pinfunction "D_7") (pintype "passive"))
      (node (ref "Q3") (pin "8") (pinfunction "D_8") (pintype "passive"))
      (node (ref "Q4") (pin "1") (pinfunction "S_1") (pintype "passive"))
      (node (ref "Q4") (pin "2") (pinfunction "S_2") (pintype "passive"))
      (node (ref "Q4") (pin "6") (pinfunction "D_6") (pintype "passive"))
      (node (ref "Q4") (pin "7") (pinfunction "D_7") (pintype "passive"))
      (node (ref "Q4") (pin "8") (pinfunction "D_8") (pintype "passive"))
      (node (ref "Q5") (pin "1") (pinfunction "S_1") (pintype "passive"))
      (node (ref "Q5") (pin "2") (pinfunction "S_2") (pintype "passive"))
      (node (ref "Q5") (pin "6") (pinfunction "D_6") (pintype "passive"))
      (node (ref "Q5") (pin "7") (pinfunction "D_7") (pintype "passive"))
      (node (ref "Q5") (pin "8") (pinfunction "D_8") (pintype "passive"))
      (node (ref "R10") (pin "1") (pinfunction "1_1") (pintype "passive"))
      (node (ref "R18") (pin "2") (pinfunction "2_2") (pintype "passive"))
      (node (ref "R32") (pin "1") (pinfunction "1_1") (pintype "passive"))
    )
    (net (code "2") (name "GND_SIGNAL") (class "Default")
      (node (ref "C14") (pin "2") (pinfunction "2_2") (pintype "passive"))
      (node (ref "C7") (pin "1") (pinfunction "1_1") (pintype "passive"))
      (node (ref "C8") (pin "1") (pinfunction "1_1") (pintype "passive"))
      (node (ref "CC1") (pin "1") (pinfunction "1_1") (pintype "passive"))
      (node (ref "CC2") (pin "1") (pinfunction "1_1") (pintype "passive"))
      (node (ref "CF1") (pin "1") (pinfunction "1_1") (pintype "passive"))
      (node (ref "CSS") (pin "2") (pinfunction "2_2") (pintype "passive"))
      (node (ref "D8") (pin "1") (pinfunction "A_1") (pintype "passive"))
      (node (ref "LTC3789") (pin "6") (pinfunction "SGND_6") (pintype "passive"))
      (node (ref "P3") (pin "3") (pinfunction "3_3") (pintype "passive"))
      (node (ref "R21") (pin "1") (pinfunction "1_1") (pintype "passive"))
      (node (ref "R24") (pin "2") (pinfunction "2_2") (pintype "passive"))
      (node (ref "R25") (pin "2") (pinfunction "2_2") (pintype "passive"))
      (node (ref "R31") (pin "2") (pinfunction "2_2") (pintype "passive"))
      (node (ref "R32") (pin "2") (pinfunction "2_2") (pintype "passive"))
      (node (ref "RFB2") (pin "2") (pinfunction "2_2") (pintype "passive"))
    )
    (net (code "3") (name "INTVCC") (class "Default")
      (node (ref "C14") (pin "1") (pinfunction "1_1") (pintype "passive"))
      (node (ref "C18") (pin "1") (pinfunction "1_1") (pintype "passive"))
      (node (ref "D4") (pin "2") (pinfunction "A_2") (pintype "passive"))
      (node (ref "D7") (pin "2") (pinfunction "A_2") (pintype "passive"))
      (node (ref "LTC3789") (pin "21") (pinfunction "INTVCC_21") (pintype "passive"))
      (node (ref "P1") (pin "1") (pinfunction "1_1") (pintype "passive"))
      (node (ref "R22") (pin "1") (pinfunction "1_1") (pintype "passive"))
      (node (ref "R7") (pin "1") (pinfunction "1_1") (pintype "passive"))
    )
    (net (code "4") (name "Net-(C12-Pad1)") (class "Default")
      (node (ref "C12") (pin "1") (pinfunction "1_1") (pintype "passive"))
      (node (ref "R28") (pin "2") (pinfunction "2_2") (pintype "passive"))
    )
    (net (code "5") (name "Net-(C13-Pad1)") (class "Default")
      (node (ref "C13") (pin "1") (pinfunction "1_1") (pintype "passive"))
      (node (ref "R29") (pin "2") (pinfunction "2_2") (pintype "passive"))
    )
    (net (code "6") (name "Net-(CC2-Pad2)") (class "Default")
      (node (ref "CC2") (pin "2") (pinfunction "2_2") (pintype "passive"))
      (node (ref "RC") (pin "2") (pinfunction "2_2") (pintype "passive"))
    )
    (net (code "7") (name "Net-(D2-A)") (class "Default")
      (node (ref "D2") (pin "1") (pinfunction "A_1") (pintype "passive"))
      (node (ref "Q5") (pin "4") (pinfunction "G_4") (pintype "passive"))
      (node (ref "R1") (pin "1") (pinfunction "1_1") (pintype "passive"))
    )
    (net (code "8") (name "Net-(D2-K)") (class "Default")
      (node (ref "D2") (pin "3") (pinfunction "K_3") (pintype "passive"))
      (node (ref "LTC3789") (pin "19") (pinfunction "BG2_19") (pintype "passive"))
      (node (ref "R1") (pin "2") (pinfunction "2_2") (pintype "passive"))
    )
    (net (code "9") (name "Net-(D4-K)") (class "Default")
      (node (ref "C4") (pin "1") (pinfunction "1_1") (pintype "passive"))
      (node (ref "D4") (pin "1") (pinfunction "K_1") (pintype "passive"))
      (node (ref "R11") (pin "2") (pinfunction "2_2") (pintype "passive"))
    )
    (net (code "10") (name "Net-(D5-A)") (class "Default")
      (node (ref "D5") (pin "2") (pinfunction "A_2") (pintype "passive"))
      (node (ref "Q4") (pin "3") (pinfunction "S_3") (pintype "passive"))
      (node (ref "Q5") (pin "3") (pinfunction "S_3") (pintype "passive"))
      (node (ref "R18") (pin "1") (pinfunction "1_1") (pintype "passive"))
      (node (ref "R29") (pin "1") (pinfunction "1_1") (pintype "passive"))
      (node (ref "R9") (pin "1") (pinfunction "1_1") (pintype "passive"))
    )
    (net (code "11") (name "Net-(D5-K)") (class "Default")
      (node (ref "C12") (pin "2") (pinfunction "2_2") (pintype "passive"))
      (node (ref "C4") (pin "2") (pinfunction "2_2") (pintype "passive"))
      (node (ref "D5") (pin "1") (pinfunction "K_1") (pintype "passive"))
      (node (ref "L1") (pin "1") (pinfunction "1_1") (pintype "passive"))
      (node (ref "LTC3789") (pin "27") (pinfunction "SW1_27") (pintype "passive"))
      (node (ref "Q2") (pin "3") (pinfunction "S_3") (pintype "passive"))
      (node (ref "Q4") (pin "5") (pinfunction "D_5") (pintype "passive"))
    )
    (net (code "12") (name "Net-(D6-A)") (class "Default")
      (node (ref "C13") (pin "2") (pinfunction "2_2") (pintype "passive"))
      (node (ref "C22") (pin "2") (pinfunction "2_2") (pintype "passive"))
      (node (ref "D6") (pin "2") (pinfunction "A_2") (pintype "passive"))
      (node (ref "L1") (pin "2") (pinfunction "2_2") (pintype "passive"))
      (node (ref "LTC3789") (pin "16") (pinfunction "SW2_16") (pintype "passive"))
      (node (ref "Q3") (pin "3") (pinfunction "S_3") (pintype "passive"))
      (node (ref "Q5") (pin "5") (pinfunction "D_5") (pintype "passive"))
    )
    (net (code "13") (name "Net-(D7-K)") (class "Default")
      (node (ref "C22") (pin "1") (pinfunction "1_1") (pintype "passive"))
      (node (ref "D7") (pin "1") (pinfunction "K_1") (pintype "passive"))
      (node (ref "LTC3789") (pin "18") (pinfunction "BOOST2_18") (pintype "passive"))
    )
    (net (code "14") (name "Net-(D8-K)") (class "Default")
      (node (ref "D8") (pin "3") (pinfunction "K_3") (pintype "passive"))
      (node (ref "LTC3789") (pin "9") (pinfunction "RUN_9") (pintype "passive"))
      (node (ref "R30") (pin "2") (pinfunction "2_2") (pintype "passive"))
      (node (ref "R31") (pin "1") (pinfunction "1_1") (pintype "passive"))
    )
    (net (code "15") (name "Net-(LTC3789-BG1)") (class "Default")
      (node (ref "LTC3789") (pin "23") (pinfunction "BG1_23") (pintype "passive"))
      (node (ref "Q4") (pin "4") (pinfunction "G_4") (pintype "passive"))
    )
    (net (code "16") (name "Net-(LTC3789-BOOST1)") (class "Default")
      (node (ref "LTC3789") (pin "25") (pinfunction "BOOST1_25") (pintype "passive"))
      (node (ref "R11") (pin "1") (pinfunction "1_1") (pintype "passive"))
    )
    (net (code "17") (name "Net-(LTC3789-EXTVCC)") (class "Default")
      (node (ref "C24") (pin "1") (pinfunction "1_1") (pintype "passive"))
      (node (ref "LTC3789") (pin "20") (pinfunction "EXTVCC_20") (pintype "passive"))
      (node (ref "R26") (pin "1") (pinfunction "1_1") (pintype "passive"))
    )
    (net (code "18") (name "Net-(LTC3789-FREQ)") (class "Default")
      (node (ref "LTC3789") (pin "8") (pinfunction "FREQ_8") (pintype "passive"))
      (node (ref "R21") (pin "2") (pinfunction "2_2") (pintype "passive"))
    )
    (net (code "19") (name "Net-(LTC3789-ILIM)") (class "Default")
      (node (ref "LTC3789") (pin "12") (pinfunction "ILIM_12") (pintype "passive"))
      (node (ref "R22") (pin "2") (pinfunction "2_2") (pintype "passive"))
      (node (ref "R25") (pin "1") (pinfunction "1_1") (pintype "passive"))
    )
    (net (code "20") (name "Net-(LTC3789-IOSENSE+)") (class "Default")
      (node (ref "C10") (pin "1") (pinfunction "1_1") (pintype "passive"))
      (node (ref "LTC3789") (pin "13") (pinfunction "IOSENSE+_13") (pintype "passive"))
      (node (ref "R12") (pin "1") (pinfunction "1_1") (pintype "passive"))
      (node (ref "R4") (pin "1") (pinfunction "1_1") (pintype "passive"))
    )
    (net (code "21") (name "Net-(LTC3789-IOSENSE-)") (class "Default")
      (node (ref "C10") (pin "2") (pinfunction "2_2") (pintype "passive"))
      (node (ref "LTC3789") (pin "14") (pinfunction "IOSENSE-_14") (pintype "passive"))
      (node (ref "R3") (pin "1") (pinfunction "1_1") (pintype "passive"))
      (node (ref "R6") (pin "1") (pinfunction "1_1") (pintype "passive"))
    )
    (net (code "22") (name "Net-(LTC3789-ITH)") (class "Default")
      (node (ref "CC1") (pin "2") (pinfunction "2_2") (pintype "passive"))
      (node (ref "LTC3789") (pin "5") (pinfunction "ITH_5") (pintype "passive"))
      (node (ref "RC") (pin "1") (pinfunction "1_1") (pintype "passive"))
    )
    (net (code "23") (name "Net-(LTC3789-MODE{slash}PLLIN)") (class "Default")
      (node (ref "LTC3789") (pin "7") (pinfunction "MODE/PLLIN_7") (pintype "passive"))
      (node (ref "P1") (pin "2") (pinfunction "2_2") (pintype "passive"))
      (node (ref "P2") (pin "1") (pinfunction "1_1") (pintype "passive"))
    )
    (net (code "24") (name "Net-(LTC3789-PGOOD)") (class "Default")
      (node (ref "LTC3789") (pin "28") (pinfunction "PGOOD_28") (pintype "passive"))
      (node (ref "R7") (pin "2") (pinfunction "2_2") (pintype "passive"))
    )
    (net (code "25") (name "Net-(LTC3789-SENSE+)") (class "Default")
      (node (ref "C11") (pin "1") (pinfunction "1_1") (pintype "passive"))
      (node (ref "LTC3789") (pin "3") (pinfunction "SENSE+_3") (pintype "passive"))
      (node (ref "R9") (pin "2") (pinfunction "2_2") (pintype "passive"))
    )
    (net (code "26") (name "Net-(LTC3789-SENSE-)") (class "Default")
      (node (ref "C11") (pin "2") (pinfunction "2_2") (pintype "passive"))
      (node (ref "LTC3789") (pin "4") (pinfunction "SENSE-_4") (pintype "passive"))
      (node (ref "R10") (pin "2") (pinfunction "2_2") (pintype "passive"))
    )
    (net (code "27") (name "Net-(LTC3789-SS)") (class "Default")
      (node (ref "CSS") (pin "1") (pinfunction "1_1") (pintype "passive"))
      (node (ref "LTC3789") (pin "2") (pinfunction "SS_2") (pintype "passive"))
    )
    (net (code "28") (name "Net-(LTC3789-TG1)") (class "Default")
      (node (ref "LTC3789") (pin "26") (pinfunction "TG1_26") (pintype "passive"))
      (node (ref "Q2") (pin "4") (pinfunction "G_4") (pintype "passive"))
    )
    (net (code "29") (name "Net-(LTC3789-TG2)") (class "Default")
      (node (ref "LTC3789") (pin "17") (pinfunction "TG2_17") (pintype "passive"))
      (node (ref "Q3") (pin "4") (pinfunction "G_4") (pintype "passive"))
    )
    (net (code "30") (name "Net-(LTC3789-VFB)") (class "Default")
      (node (ref "CF") (pin "2") (pinfunction "2_2") (pintype "passive"))
      (node (ref "CF1") (pin "2") (pinfunction "2_2") (pintype "passive"))
      (node (ref "LTC3789") (pin "1") (pinfunction "VFB_1") (pintype "passive"))
      (node (ref "RFB1") (pin "2") (pinfunction "2_2") (pintype "passive"))
      (node (ref "RFB2") (pin "1") (pinfunction "1_1") (pintype "passive"))
    )
    (net (code "31") (name "Net-(LTC3789-VIN)") (class "Default")
      (node (ref "C15") (pin "1") (pinfunction "1_1") (pintype "passive"))
      (node (ref "LTC3789") (pin "22") (pinfunction "VIN_22") (pintype "passive"))
      (node (ref "R5") (pin "1") (pinfunction "1_1") (pintype "passive"))
    )
    (net (code "32") (name "Net-(LTC3789-VINSNS)") (class "Default")
      (node (ref "C7") (pin "2") (pinfunction "2_2") (pintype "passive"))
      (node (ref "LTC3789") (pin "10") (pinfunction "VINSNS_10") (pintype "passive"))
      (node (ref "R13") (pin "1") (pinfunction "1_1") (pintype "passive"))
    )
    (net (code "33") (name "Net-(LTC3789-VOUTSNS)") (class "Default")
      (node (ref "C8") (pin "2") (pinfunction "2_2") (pintype "passive"))
      (node (ref "LTC3789") (pin "11") (pinfunction "VOUTSNS_11") (pintype "passive"))
      (node (ref "R14") (pin "1") (pinfunction "1_1") (pintype "passive"))
    )
    (net (code "34") (name "Net-(P2-Pad2)") (class "Default")
      (node (ref "P2") (pin "2") (pinfunction "2_2") (pintype "passive"))
      (node (ref "R24") (pin "1") (pinfunction "1_1") (pintype "passive"))
    )
    (net (code "35") (name "Net-(P3-Pad2)") (class "Default")
      (node (ref "P3") (pin "2") (pinfunction "2_2") (pintype "passive"))
      (node (ref "R30") (pin "1") (pinfunction "1_1") (pintype "passive"))
    )
    (net (code "36") (name "VIN") (class "Default")
      (node (ref "C25") (pin "1") (pinfunction "A_1") (pintype "passive"))
      (node (ref "C26") (pin "1") (pinfunction "1_1") (pintype "passive"))
      (node (ref "C27") (pin "1") (pinfunction "1_1") (pintype "passive"))
      (node (ref "C9") (pin "1") (pinfunction "A_1") (pintype "passive"))
      (node (ref "Q2") (pin "5") (pinfunction "D_5") (pintype "passive"))
      (node (ref "R13") (pin "2") (pinfunction "2_2") (pintype "passive"))
      (node (ref "R20") (pin "2") (pinfunction "2_2") (pintype "passive"))
      (node (ref "R28") (pin "1") (pinfunction "1_1") (pintype "passive"))
      (node (ref "R5") (pin "2") (pinfunction "2_2") (pintype "passive"))
      (node (ref "R6") (pin "2") (pinfunction "2_2") (pintype "passive"))
    )
    (net (code "37") (name "VIN+") (class "Default")
      (node (ref "C5") (pin "1") (pinfunction "A_1") (pintype "passive"))
      (node (ref "C6") (pin "1") (pinfunction "A_1") (pintype "passive"))
      (node (ref "CIN1") (pin "1") (pinfunction "A_1") (pintype "passive"))
      (node (ref "CIN2") (pin "1") (pinfunction "A_1") (pintype "passive"))
      (node (ref "J3") (pin "1") (pinfunction "1_1") (pintype "passive"))
      (node (ref "P3") (pin "1") (pinfunction "1_1") (pintype "passive"))
      (node (ref "R12") (pin "2") (pinfunction "2_2") (pintype "passive"))
      (node (ref "R20") (pin "1") (pinfunction "1_1") (pintype "passive"))
    )
    (net (code "38") (name "VOS+") (class "Default")
      (node (ref "CF") (pin "1") (pinfunction "1_1") (pintype "passive"))
      (node (ref "R8") (pin "1") (pinfunction "1_1") (pintype "passive"))
      (node (ref "RFB1") (pin "1") (pinfunction "1_1") (pintype "passive"))
    )
    (net (code "39") (name "VOUT") (class "Default")
      (node (ref "C3") (pin "1") (pinfunction "1_1") (pintype "passive"))
      (node (ref "COUT1") (pin "1") (pinfunction "A_1") (pintype "passive"))
      (node (ref "COUT2") (pin "1") (pinfunction "A_1") (pintype "passive"))
      (node (ref "J1") (pin "1") (pinfunction "1_1") (pintype "passive"))
      (node (ref "R14") (pin "2") (pinfunction "2_2") (pintype "passive"))
      (node (ref "R2") (pin "1") (pinfunction "1_1") (pintype "passive"))
      (node (ref "R26") (pin "2") (pinfunction "2_2") (pintype "passive"))
      (node (ref "R3") (pin "2") (pinfunction "2_2") (pintype "passive"))
      (node (ref "R8") (pin "2") (pinfunction "2_2") (pintype "passive"))
    )
    (net (code "40") (name "VOUT1") (class "Default")
      (node (ref "C1") (pin "2") (pinfunction "2_2") (pintype "passive"))
      (node (ref "C16") (pin "2") (pinfunction "2_2") (pintype "passive"))
      (node (ref "C2") (pin "2") (pinfunction "2_2") (pintype "passive"))
      (node (ref "D6") (pin "1") (pinfunction "K_1") (pintype "passive"))
      (node (ref "Q3") (pin "5") (pinfunction "D_5") (pintype "passive"))
      (node (ref "R2") (pin "2") (pinfunction "2_2") (pintype "passive"))
      (node (ref "R4") (pin "2") (pinfunction "2_2") (pintype "passive"))
    )
    (net (code "41") (name "unconnected-(D2-not_connected-Pad2)") (class "Default")
      (node (ref "D2") (pin "2") (pinfunction "not_connected_2") (pintype "passive"))
    )
    (net (code "42") (name "unconnected-(D8-not_connected-Pad2)") (class "Default")
      (node (ref "D8") (pin "2") (pinfunction "not_connected_2") (pintype "passive"))
    )
  )
)
